# Sheet3.net
KiCad netlist of a schematic drawn in Altium Designer
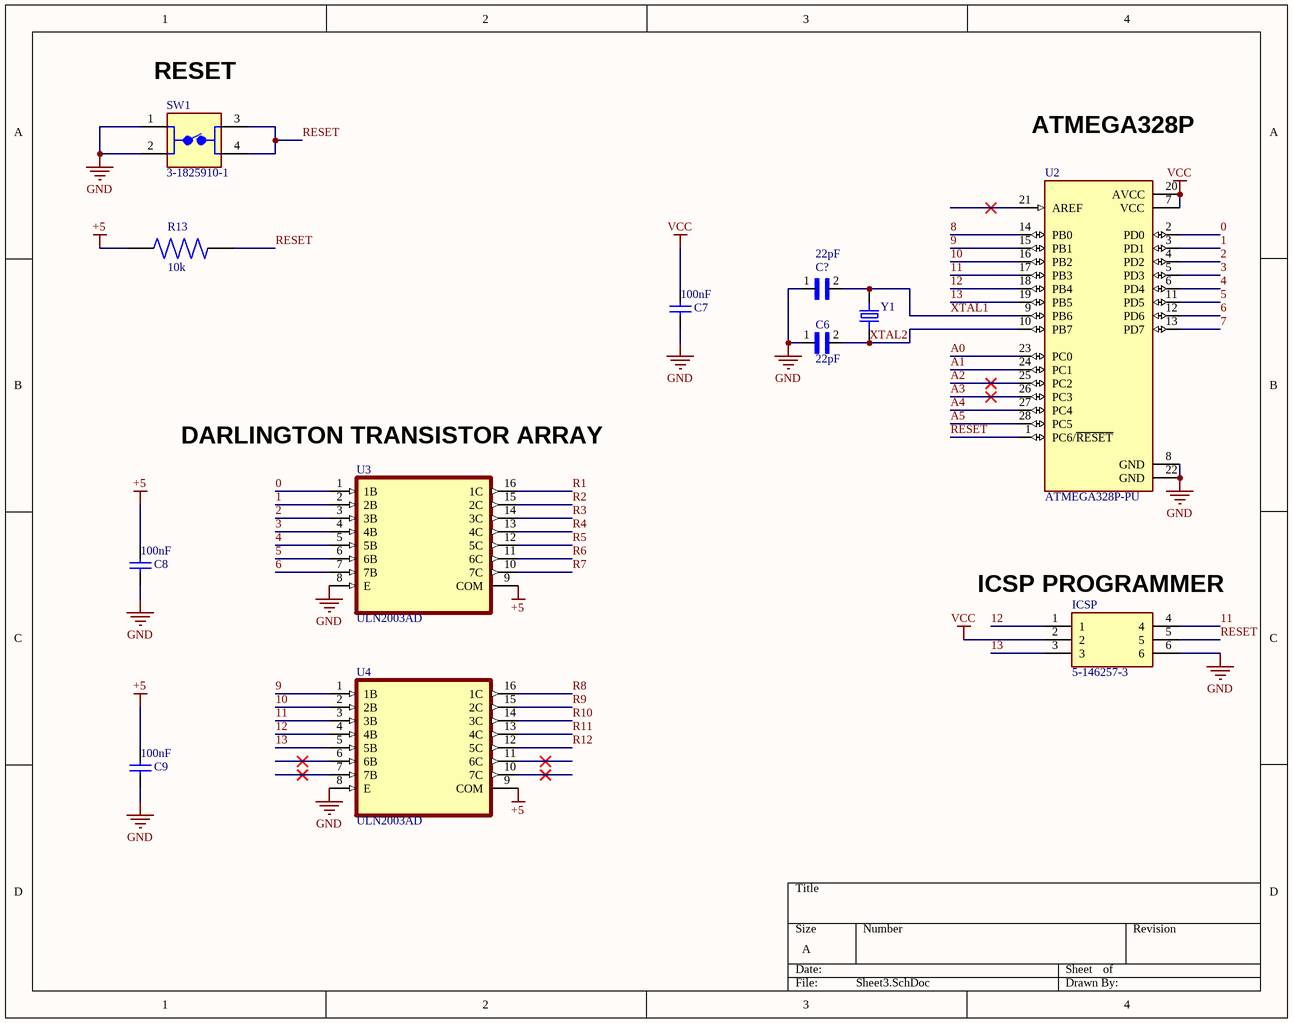
[diagram p0: Sheet3.SchDoc]

(export (version "E")
  (design (tool "Eeschema 10.0.6"))
  (components
    (comp (ref "C5")
      (value "22pF")
      (footprint "control:CAPC2012X130N")
      (description "Cap Cer 22pf 50v C0g/Np0 0805")
      (fields
        (field (name "ALTIUM_VALUE") "C?")
        (field (name "MF") "Syfer")
        (field (name "MP") "0805Y0500220JCT")
      )
      (libsource (lib "control") (part "0805Y0500220JCT"))
    )
    (comp (ref "C6")
      (value "22pF")
      (footprint "control:CAPC2012X130N")
      (description "Cap Cer 22pf 50v C0g/Np0 0805")
      (fields (field (name "MF") "Syfer") (field (name "MP") "0805Y0500220JCT"))
      (libsource (lib "control") (part "0805Y0500220JCT"))
    )
    (comp (ref "C7")
      (value "100nF")
      (footprint "WCAP-CSGP_0603_L1.6W0.8H0.8_Wave")
      (description "WCAP-CSGP Multilayer Ceramic Chip Capacitor, General Purpose, size 0603, X7R, 100nF, 25VDC")
      (fields
        (field (name "MANUFACTURER PART NUMBER") "885012206071")
        (field (name "MANUFACTURER") "Wurth Elektronik")
      )
      (libsource (lib "input") (part "885012206071"))
    )
    (comp (ref "C8")
      (value "100nF")
      (footprint "WCAP-CSGP_0603_L1.6W0.8H0.8_Wave")
      (description "WCAP-CSGP Multilayer Ceramic Chip Capacitor, General Purpose, size 0603, X7R, 100nF, 25VDC")
      (fields
        (field (name "MANUFACTURER PART NUMBER") "885012206071")
        (field (name "MANUFACTURER") "Wurth Elektronik")
      )
      (libsource (lib "input") (part "885012206071"))
    )
    (comp (ref "C9")
      (value "100nF")
      (footprint "WCAP-CSGP_0603_L1.6W0.8H0.8_Wave")
      (description "WCAP-CSGP Multilayer Ceramic Chip Capacitor, General Purpose, size 0603, X7R, 100nF, 25VDC")
      (fields
        (field (name "MANUFACTURER PART NUMBER") "885012206071")
        (field (name "MANUFACTURER") "Wurth Elektronik")
      )
      (libsource (lib "input") (part "885012206071"))
    )
    (comp (ref "ICSP")
      (value "5-146257-3")
      (footprint "TE_5-146257-3")
      (description "Header; Breakaway; 0.100 x 0.100 in.; PC Board; Dual; 6; 0.025 in.; 0.12 in.")
      (fields (field (name "MF") "TE Connectivity"))
      (libsource (lib "control") (part "5-146257-3"))
    )
    (comp (ref "R13")
      (value "10k")
      (footprint "RESC3216X70N")
      (description "Res 1206 10 Ohm 5% 1/8W Â±500ppm/Â°C Molded SMD SMD T/R")
      (fields (field (name "TOLERANCE") "5%") (field (name "MP") "FCR1206J10R"))
      (libsource (lib "input") (part "FCR1206J10R"))
    )
    (comp (ref "SW1")
      (value "3-1825910-1")
      (footprint "TE_3-1825910-1")
      (description "Switch Push Button OFF (ON) SPST Round Button 0.05A 24VDC Momentary Contact PC Pins Thru-Hole")
      (fields (field (name "MF") "TE Connectivity"))
      (libsource (lib "control") (part "3-1825910-1"))
    )
    (comp (ref "U2")
      (value "ATMEGA328P-PU")
      (footprint "control:DIP794W46P254L2967H457Q28B")
      (description "ATmega Series 20 MHz 32 KB Flash 2 KB SRAM 8-Bit Microcontroller - DIP-28")
      (libsource (lib "control") (part "ATMEGA328P-PU"))
    )
    (comp (ref "U3")
      (value "ULN2003AD")
      (footprint "SOIC127P600X175-16N")
      (description "50-V, 7-ch darlington transistor array, -20C to 70C")
      (fields (field (name "MF") "Texas Instruments"))
      (libsource (lib "control") (part "ULN2003AD"))
    )
    (comp (ref "U4")
      (value "ULN2003AD")
      (footprint "SOIC127P600X175-16N")
      (description "50-V, 7-ch darlington transistor array, -20C to 70C")
      (fields (field (name "MF") "Texas Instruments"))
      (libsource (lib "control") (part "ULN2003AD"))
    )
    (comp (ref "Y1")
      (value "~")
      (footprint "control:XTAL_ECS-160-20-3X-TR")
      (description "16MHz Â±30ppm Crystal 20pF 50 Ohms HC-49/US")
      (fields (field (name "DIGI-KEY_PART_NUMBER") "XC1776CT-ND") (field (name "MP") "ECS-160-20-3X-TR"))
      (libsource (lib "control") (part "ECS-160-20-3X-TR"))
    )
  )
  (nets
    (net (code "1") (name "+5") (class "Default")
      (node (ref "C8") (pin "2") (pinfunction "2_2") (pintype "passive"))
      (node (ref "C9") (pin "2") (pinfunction "2_2") (pintype "passive"))
      (node (ref "R13") (pin "1") (pinfunction "1_1") (pintype "passive"))
      (node (ref "U3") (pin "9") (pinfunction "COM_9") (pintype "power_in"))
      (node (ref "U4") (pin "9") (pinfunction "COM_9") (pintype "power_in"))
    )
    (net (code "2") (name "/0") (class "Default")
      (node (ref "U2") (pin "2") (pinfunction "PD0_2") (pintype "bidirectional"))
      (node (ref "U3") (pin "1") (pinfunction "1B_1") (pintype "input"))
    )
    (net (code "3") (name "/1") (class "Default")
      (node (ref "U2") (pin "3") (pinfunction "PD1_3") (pintype "bidirectional"))
      (node (ref "U3") (pin "2") (pinfunction "2B_2") (pintype "input"))
    )
    (net (code "4") (name "/2") (class "Default")
      (node (ref "U2") (pin "4") (pinfunction "PD2_4") (pintype "bidirectional"))
      (node (ref "U3") (pin "3") (pinfunction "3B_3") (pintype "input"))
    )
    (net (code "5") (name "/3") (class "Default")
      (node (ref "U2") (pin "5") (pinfunction "PD3_5") (pintype "bidirectional"))
      (node (ref "U3") (pin "4") (pinfunction "4B_4") (pintype "input"))
    )
    (net (code "6") (name "/4") (class "Default")
      (node (ref "U2") (pin "6") (pinfunction "PD4_6") (pintype "bidirectional"))
      (node (ref "U3") (pin "5") (pinfunction "5B_5") (pintype "input"))
    )
    (net (code "7") (name "/5") (class "Default")
      (node (ref "U2") (pin "11") (pinfunction "PD5_11") (pintype "bidirectional"))
      (node (ref "U3") (pin "6") (pinfunction "6B_6") (pintype "input"))
    )
    (net (code "8") (name "/6") (class "Default")
      (node (ref "U2") (pin "12") (pinfunction "PD6_12") (pintype "bidirectional"))
      (node (ref "U3") (pin "7") (pinfunction "7B_7") (pintype "input"))
    )
    (net (code "9") (name "/7") (class "Default")
      (node (ref "U2") (pin "13") (pinfunction "PD7_13") (pintype "bidirectional"))
    )
    (net (code "10") (name "/8") (class "Default")
      (node (ref "U2") (pin "14") (pinfunction "PB0_14") (pintype "bidirectional"))
    )
    (net (code "11") (name "/9") (class "Default")
      (node (ref "U2") (pin "15") (pinfunction "PB1_15") (pintype "bidirectional"))
      (node (ref "U4") (pin "1") (pinfunction "1B_1") (pintype "input"))
    )
    (net (code "12") (name "/10") (class "Default")
      (node (ref "U2") (pin "16") (pinfunction "PB2_16") (pintype "bidirectional"))
      (node (ref "U4") (pin "2") (pinfunction "2B_2") (pintype "input"))
    )
    (net (code "13") (name "/11") (class "Default")
      (node (ref "ICSP") (pin "4") (pinfunction "4_4") (pintype "passive"))
      (node (ref "U2") (pin "17") (pinfunction "PB3_17") (pintype "bidirectional"))
      (node (ref "U4") (pin "3") (pinfunction "3B_3") (pintype "input"))
    )
    (net (code "14") (name "/12") (class "Default")
      (node (ref "ICSP") (pin "1") (pinfunction "1_1") (pintype "passive"))
      (node (ref "U2") (pin "18") (pinfunction "PB4_18") (pintype "bidirectional"))
      (node (ref "U4") (pin "4") (pinfunction "4B_4") (pintype "input"))
    )
    (net (code "15") (name "/13") (class "Default")
      (node (ref "ICSP") (pin "3") (pinfunction "3_3") (pintype "passive"))
      (node (ref "U2") (pin "19") (pinfunction "PB5_19") (pintype "bidirectional"))
      (node (ref "U4") (pin "5") (pinfunction "5B_5") (pintype "input"))
    )
    (net (code "16") (name "/A0") (class "Default")
      (node (ref "U2") (pin "23") (pinfunction "PC0_23") (pintype "bidirectional"))
    )
    (net (code "17") (name "/A1") (class "Default")
      (node (ref "U2") (pin "24") (pinfunction "PC1_24") (pintype "bidirectional"))
    )
    (net (code "18") (name "/A2") (class "Default")
      (node (ref "U2") (pin "25") (pinfunction "PC2_25") (pintype "bidirectional"))
    )
    (net (code "19") (name "/A3") (class "Default")
      (node (ref "U2") (pin "26") (pinfunction "PC3_26") (pintype "bidirectional"))
    )
    (net (code "20") (name "/A4") (class "Default")
      (node (ref "U2") (pin "27") (pinfunction "PC4_27") (pintype "bidirectional"))
    )
    (net (code "21") (name "/A5") (class "Default")
      (node (ref "U2") (pin "28") (pinfunction "PC5_28") (pintype "bidirectional"))
    )
    (net (code "22") (name "/R1") (class "Default")
      (node (ref "U3") (pin "16") (pinfunction "1C_16") (pintype "output"))
    )
    (net (code "23") (name "/R2") (class "Default")
      (node (ref "U3") (pin "15") (pinfunction "2C_15") (pintype "output"))
    )
    (net (code "24") (name "/R3") (class "Default")
      (node (ref "U3") (pin "14") (pinfunction "3C_14") (pintype "output"))
    )
    (net (code "25") (name "/R4") (class "Default")
      (node (ref "U3") (pin "13") (pinfunction "4C_13") (pintype "output"))
    )
    (net (code "26") (name "/R5") (class "Default")
      (node (ref "U3") (pin "12") (pinfunction "5C_12") (pintype "output"))
    )
    (net (code "27") (name "/R6") (class "Default")
      (node (ref "U3") (pin "11") (pinfunction "6C_11") (pintype "output"))
    )
    (net (code "28") (name "/R7") (class "Default")
      (node (ref "U3") (pin "10") (pinfunction "7C_10") (pintype "output"))
    )
    (net (code "29") (name "/R8") (class "Default")
      (node (ref "U4") (pin "16") (pinfunction "1C_16") (pintype "output"))
    )
    (net (code "30") (name "/R9") (class "Default")
      (node (ref "U4") (pin "15") (pinfunction "2C_15") (pintype "output"))
    )
    (net (code "31") (name "/R10") (class "Default")
      (node (ref "U4") (pin "14") (pinfunction "3C_14") (pintype "output"))
    )
    (net (code "32") (name "/R11") (class "Default")
      (node (ref "U4") (pin "13") (pinfunction "4C_13") (pintype "output"))
    )
    (net (code "33") (name "/R12") (class "Default")
      (node (ref "U4") (pin "12") (pinfunction "5C_12") (pintype "output"))
    )
    (net (code "34") (name "/RESET") (class "Default")
      (node (ref "ICSP") (pin "5") (pinfunction "5_5") (pintype "passive"))
      (node (ref "R13") (pin "2") (pinfunction "2_2") (pintype "passive"))
      (node (ref "SW1") (pin "3") (pinfunction "3_3") (pintype "passive"))
      (node (ref "SW1") (pin "4") (pinfunction "4_4") (pintype "passive"))
      (node (ref "U2") (pin "1") (pinfunction "PC6/~{RESET}_1") (pintype "bidirectional"))
    )
    (net (code "35") (name "/XTAL1") (class "Default")
      (node (ref "C5") (pin "2") (pinfunction "2_2") (pintype "passive"))
      (node (ref "U2") (pin "9") (pinfunction "PB6_9") (pintype "bidirectional"))
      (node (ref "Y1") (pin "2") (pinfunction "2_2") (pintype "passive"))
    )
    (net (code "36") (name "/XTAL2") (class "Default")
      (node (ref "C6") (pin "2") (pinfunction "2_2") (pintype "passive"))
      (node (ref "U2") (pin "10") (pinfunction "PB7_10") (pintype "bidirectional"))
      (node (ref "Y1") (pin "1") (pinfunction "1_1") (pintype "passive"))
    )
    (net (code "37") (name "GND") (class "Default")
      (node (ref "C5") (pin "1") (pinfunction "1_1") (pintype "passive"))
      (node (ref "C6") (pin "1") (pinfunction "1_1") (pintype "passive"))
      (node (ref "C7") (pin "1") (pinfunction "1_1") (pintype "passive"))
      (node (ref "C8") (pin "1") (pinfunction "1_1") (pintype "passive"))
      (node (ref "C9") (pin "1") (pinfunction "1_1") (pintype "passive"))
      (node (ref "ICSP") (pin "6") (pinfunction "6_6") (pintype "passive"))
      (node (ref "SW1") (pin "1") (pinfunction "1_1") (pintype "passive"))
      (node (ref "SW1") (pin "2") (pinfunction "2_2") (pintype "passive"))
      (node (ref "U2") (pin "22") (pinfunction "GND_22") (pintype "power_in"))
      (node (ref "U2") (pin "8") (pinfunction "GND_8") (pintype "power_in"))
      (node (ref "U3") (pin "8") (pinfunction "E_8") (pintype "input"))
      (node (ref "U4") (pin "8") (pinfunction "E_8") (pintype "input"))
    )
    (net (code "38") (name "VCC") (class "Default")
      (node (ref "C7") (pin "2") (pinfunction "2_2") (pintype "passive"))
      (node (ref "ICSP") (pin "2") (pinfunction "2_2") (pintype "passive"))
      (node (ref "U2") (pin "20") (pinfunction "AVCC_20") (pintype "power_in"))
      (node (ref "U2") (pin "7") (pinfunction "VCC_7") (pintype "power_in"))
    )
    (net (code "39") (name "unconnected-(U2-AREF-Pad21)") (class "Default")
      (node (ref "U2") (pin "21") (pinfunction "AREF_21") (pintype "input"))
    )
    (net (code "40") (name "unconnected-(U4-6B-Pad6)") (class "Default")
      (node (ref "U4") (pin "6") (pinfunction "6B_6") (pintype "input"))
    )
    (net (code "41") (name "unconnected-(U4-6C-Pad11)") (class "Default")
      (node (ref "U4") (pin "11") (pinfunction "6C_11") (pintype "output"))
    )
    (net (code "42") (name "unconnected-(U4-7B-Pad7)") (class "Default")
      (node (ref "U4") (pin "7") (pinfunction "7B_7") (pintype "input"))
    )
    (net (code "43") (name "unconnected-(U4-7C-Pad10)") (class "Default")
      (node (ref "U4") (pin "10") (pinfunction "7C_10") (pintype "output"))
    )
  )
)
